# imager-adc.net
KiCad netlist of a schematic drawn in EAGLE
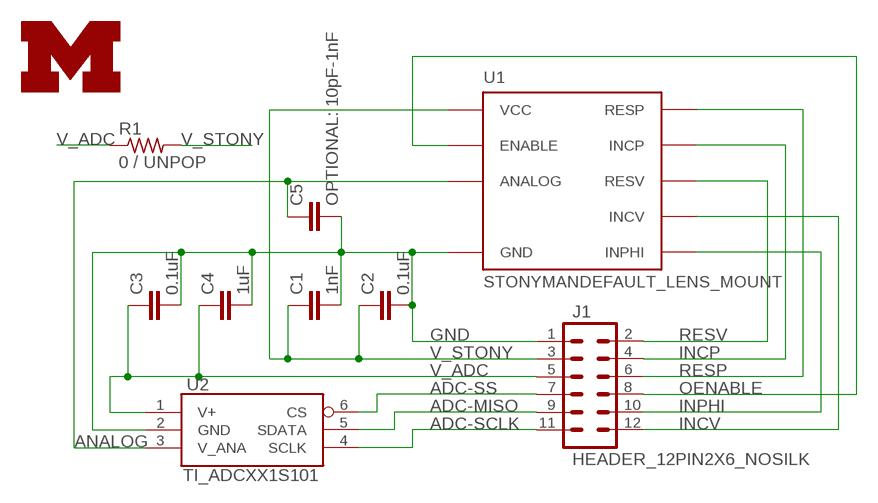
[diagram p0: schematic, sheet 1]

(export (version "E")
  (design (tool "Eeschema 10.0.6"))
  (components
    (comp (ref "C1")
      (value "1nF")
      (footprint "eagle-import:C0603")
      (libsource (lib "eagle-import") (part "C-EUC0603"))
    )
    (comp (ref "C2")
      (value "0.1uF")
      (footprint "eagle-import:C0603")
      (libsource (lib "eagle-import") (part "C-EUC0603"))
    )
    (comp (ref "C3")
      (value "0.1uF")
      (footprint "eagle-import:C0603")
      (libsource (lib "eagle-import") (part "C-EUC0603"))
    )
    (comp (ref "C4")
      (value "1uF")
      (footprint "eagle-import:C0603")
      (libsource (lib "eagle-import") (part "C-EUC0603"))
    )
    (comp (ref "C5")
      (value "OPTIONAL: 10pF-1nF")
      (footprint "eagle-import:C0603")
      (libsource (lib "eagle-import") (part "C-EUC0603"))
    )
    (comp (ref "J1")
      (value "HEADER_12PIN2X6_NOSILK")
      (footprint "eagle-import:HEADER2X6_0.05IN_NO_SILK")
      (libsource (lib "eagle-import") (part "HEADER_12PIN2X6_NOSILK"))
    )
    (comp (ref "R1")
      (value "0 / UNPOP")
      (footprint "eagle-import:R0603")
      (libsource (lib "eagle-import") (part "R-US_R0603"))
    )
    (comp (ref "U$1")
      (value "UMICH_SOLID_SMALL")
      (footprint "eagle-import:UMICH_SOLID_75MIL")
      (libsource (lib "eagle-import") (part "UMICH_SOLID_SMALL"))
    )
    (comp (ref "U1")
      (value "STONYMANDEFAULT_LENS_MOUNT")
      (footprint "eagle-import:STONYMAN_DEFAULT_LENS")
      (libsource (lib "eagle-import") (part "STONYMANDEFAULT_LENS_MOUNT"))
    )
    (comp (ref "U2")
      (value "TI_ADCXX1S101")
      (footprint "eagle-import:SOT23-6")
      (libsource (lib "eagle-import") (part "TI_ADCXX1S101"))
    )
  )
  (nets
    (net (code "1") (name "ADC-MISO") (class "Default")
      (node (ref "J1") (pin "9") (pinfunction "9_9") (pintype "passive"))
      (node (ref "U2") (pin "5") (pinfunction "SDATA_5") (pintype "bidirectional"))
    )
    (net (code "2") (name "ADC-SCLK") (class "Default")
      (node (ref "J1") (pin "11") (pinfunction "11_11") (pintype "passive"))
      (node (ref "U2") (pin "4") (pinfunction "SCLK_4") (pintype "bidirectional"))
    )
    (net (code "3") (name "ADC-SS") (class "Default")
      (node (ref "J1") (pin "7") (pinfunction "7_7") (pintype "passive"))
      (node (ref "U2") (pin "6") (pinfunction "CS_6") (pintype "bidirectional"))
    )
    (net (code "4") (name "ANALOG") (class "Default")
      (node (ref "C5") (pin "1") (pinfunction "1_1") (pintype "passive"))
      (node (ref "U1") (pin "P$8") (pinfunction "ANALOG_P$8") (pintype "output"))
      (node (ref "U2") (pin "3") (pinfunction "V_ANA_3") (pintype "bidirectional"))
    )
    (net (code "5") (name "GND") (class "Default")
      (node (ref "C1") (pin "2") (pinfunction "2_2") (pintype "passive"))
      (node (ref "C2") (pin "2") (pinfunction "2_2") (pintype "passive"))
      (node (ref "C3") (pin "2") (pinfunction "2_2") (pintype "passive"))
      (node (ref "C4") (pin "2") (pinfunction "2_2") (pintype "passive"))
      (node (ref "C5") (pin "2") (pinfunction "2_2") (pintype "passive"))
      (node (ref "J1") (pin "1") (pinfunction "1_1") (pintype "passive"))
      (node (ref "U1") (pin "P$1") (pinfunction "GND_P$1") (pintype "power_in"))
      (node (ref "U1") (pin "P$10") (pinfunction "GND_P$10") (pintype "power_in"))
      (node (ref "U2") (pin "2") (pinfunction "GND_2") (pintype "bidirectional"))
    )
    (net (code "6") (name "INCP") (class "Default")
      (node (ref "J1") (pin "4") (pinfunction "4_4") (pintype "passive"))
      (node (ref "U1") (pin "P$4") (pinfunction "INCP_P$4") (pintype "input"))
    )
    (net (code "7") (name "INCV") (class "Default")
      (node (ref "J1") (pin "12") (pinfunction "12_12") (pintype "passive"))
      (node (ref "U1") (pin "P$6") (pinfunction "INCV_P$6") (pintype "input"))
    )
    (net (code "8") (name "INPHI") (class "Default")
      (node (ref "J1") (pin "10") (pinfunction "10_10") (pintype "passive"))
      (node (ref "U1") (pin "P$7") (pinfunction "INPHI_P$7") (pintype "input"))
    )
    (net (code "9") (name "OENABLE") (class "Default")
      (node (ref "J1") (pin "8") (pinfunction "8_8") (pintype "passive"))
      (node (ref "U1") (pin "P$9") (pinfunction "ENABLE_P$9") (pintype "input"))
    )
    (net (code "10") (name "RESP") (class "Default")
      (node (ref "J1") (pin "6") (pinfunction "6_6") (pintype "passive"))
      (node (ref "U1") (pin "P$3") (pinfunction "RESP_P$3") (pintype "input"))
    )
    (net (code "11") (name "RESV") (class "Default")
      (node (ref "J1") (pin "2") (pinfunction "2_2") (pintype "passive"))
      (node (ref "U1") (pin "P$5") (pinfunction "RESV_P$5") (pintype "input"))
    )
    (net (code "12") (name "V_ADC") (class "Default")
      (node (ref "C3") (pin "1") (pinfunction "1_1") (pintype "passive"))
      (node (ref "C4") (pin "1") (pinfunction "1_1") (pintype "passive"))
      (node (ref "J1") (pin "5") (pinfunction "5_5") (pintype "passive"))
      (node (ref "R1") (pin "1") (pinfunction "1_1") (pintype "passive"))
      (node (ref "U2") (pin "1") (pinfunction "V+_1") (pintype "bidirectional"))
    )
    (net (code "13") (name "V_STONY") (class "Default")
      (node (ref "C1") (pin "1") (pinfunction "1_1") (pintype "passive"))
      (node (ref "C2") (pin "1") (pinfunction "1_1") (pintype "passive"))
      (node (ref "J1") (pin "3") (pinfunction "3_3") (pintype "passive"))
      (node (ref "R1") (pin "2") (pinfunction "2_2") (pintype "passive"))
      (node (ref "U1") (pin "P$2") (pinfunction "VCC_P$2") (pintype "power_in"))
    )
  )
)
